# bot_schem_rev3.net
KiCad netlist of a schematic drawn in Altium Designer
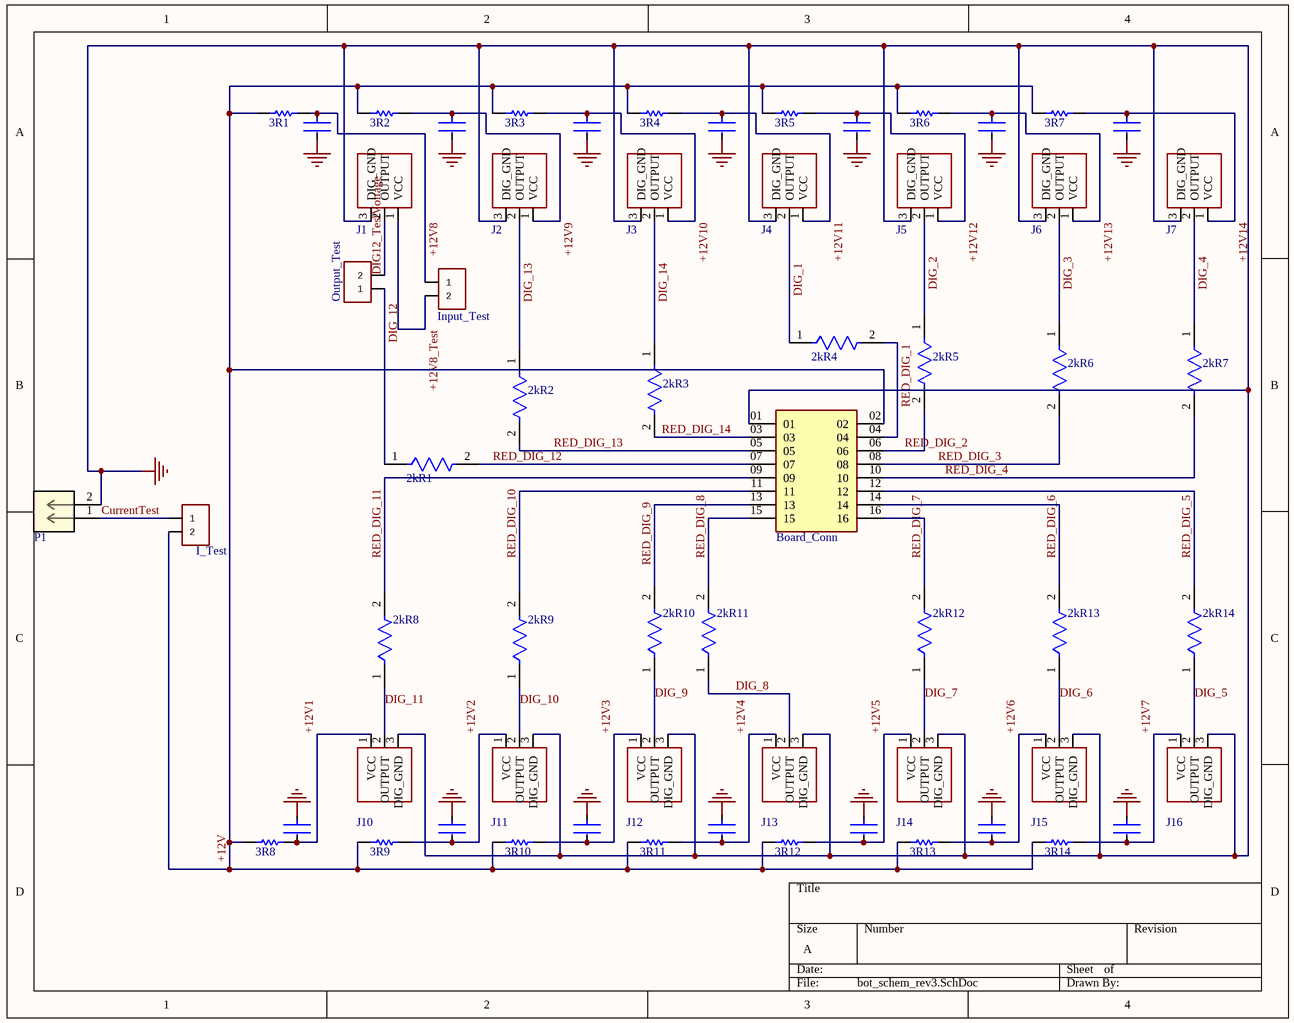
[diagram p0: bot_schem_rev3.SchDoc]

(export (version "E")
  (design (tool "Eeschema 10.0.6"))
  (components
    (comp (ref "2kR1")
      (value "CRCW06031K80FKEA")
      (footprint "2kOhm")
      (description "Res Thick Film 0603 1.8K Ohm 1% 1/10W ±100ppm/°C Molded SMD Paper T/R")
      (fields (field (name "MANUFACTURER") "Vishay") (field (name "TOLERANCE") "1%"))
      (libsource (lib "ps_schlib") (part "CRCW06031K80FKEA"))
    )
    (comp (ref "2kR2")
      (value "CRCW06031K80FKEA")
      (footprint "2kOhm")
      (description "Res Thick Film 0603 1.8K Ohm 1% 1/10W ±100ppm/°C Molded SMD Paper T/R")
      (fields (field (name "MANUFACTURER") "Vishay") (field (name "TOLERANCE") "1%"))
      (libsource (lib "ps_schlib") (part "CRCW06031K80FKEA"))
    )
    (comp (ref "2kR3")
      (value "CRCW06031K80FKEA")
      (footprint "2kOhm")
      (description "Res Thick Film 0603 1.8K Ohm 1% 1/10W ±100ppm/°C Molded SMD Paper T/R")
      (fields (field (name "MANUFACTURER") "Vishay") (field (name "TOLERANCE") "1%"))
      (libsource (lib "ps_schlib") (part "CRCW06031K80FKEA"))
    )
    (comp (ref "2kR4")
      (value "CRCW06031K80FKEA")
      (footprint "2kOhm")
      (description "Res Thick Film 0603 1.8K Ohm 1% 1/10W ±100ppm/°C Molded SMD Paper T/R")
      (fields (field (name "MANUFACTURER") "Vishay") (field (name "TOLERANCE") "1%"))
      (libsource (lib "ps_schlib") (part "CRCW06031K80FKEA"))
    )
    (comp (ref "2kR5")
      (value "CRCW06031K80FKEA")
      (footprint "2kOhm")
      (description "Res Thick Film 0603 1.8K Ohm 1% 1/10W ±100ppm/°C Molded SMD Paper T/R")
      (fields (field (name "MANUFACTURER") "Vishay") (field (name "TOLERANCE") "1%"))
      (libsource (lib "ps_schlib") (part "CRCW06031K80FKEA"))
    )
    (comp (ref "2kR6")
      (value "CRCW06031K80FKEA")
      (footprint "2kOhm")
      (description "Res Thick Film 0603 1.8K Ohm 1% 1/10W ±100ppm/°C Molded SMD Paper T/R")
      (fields (field (name "MANUFACTURER") "Vishay") (field (name "TOLERANCE") "1%"))
      (libsource (lib "ps_schlib") (part "CRCW06031K80FKEA"))
    )
    (comp (ref "2kR7")
      (value "CRCW06031K80FKEA")
      (footprint "2kOhm")
      (description "Res Thick Film 0603 1.8K Ohm 1% 1/10W ±100ppm/°C Molded SMD Paper T/R")
      (fields (field (name "MANUFACTURER") "Vishay") (field (name "TOLERANCE") "1%"))
      (libsource (lib "ps_schlib") (part "CRCW06031K80FKEA"))
    )
    (comp (ref "2kR8")
      (value "CRCW06031K80FKEA")
      (footprint "2kOhm")
      (description "Res Thick Film 0603 1.8K Ohm 1% 1/10W ±100ppm/°C Molded SMD Paper T/R")
      (fields (field (name "MANUFACTURER") "Vishay") (field (name "TOLERANCE") "1%"))
      (libsource (lib "ps_schlib") (part "CRCW06031K80FKEA"))
    )
    (comp (ref "2kR9")
      (value "CRCW06031K80FKEA")
      (footprint "2kOhm")
      (description "Res Thick Film 0603 1.8K Ohm 1% 1/10W ±100ppm/°C Molded SMD Paper T/R")
      (fields (field (name "MANUFACTURER") "Vishay") (field (name "TOLERANCE") "1%"))
      (libsource (lib "ps_schlib") (part "CRCW06031K80FKEA"))
    )
    (comp (ref "2kR10")
      (value "CRCW06031K80FKEA")
      (footprint "2kOhm")
      (description "Res Thick Film 0603 1.8K Ohm 1% 1/10W ±100ppm/°C Molded SMD Paper T/R")
      (fields (field (name "MANUFACTURER") "Vishay") (field (name "TOLERANCE") "1%"))
      (libsource (lib "ps_schlib") (part "CRCW06031K80FKEA"))
    )
    (comp (ref "2kR11")
      (value "CRCW06031K80FKEA")
      (footprint "2kOhm")
      (description "Res Thick Film 0603 1.8K Ohm 1% 1/10W ±100ppm/°C Molded SMD Paper T/R")
      (fields (field (name "MANUFACTURER") "Vishay") (field (name "TOLERANCE") "1%"))
      (libsource (lib "ps_schlib") (part "CRCW06031K80FKEA"))
    )
    (comp (ref "2kR12")
      (value "CRCW06031K80FKEA")
      (footprint "2kOhm")
      (description "Res Thick Film 0603 1.8K Ohm 1% 1/10W ±100ppm/°C Molded SMD Paper T/R")
      (fields (field (name "MANUFACTURER") "Vishay") (field (name "TOLERANCE") "1%"))
      (libsource (lib "ps_schlib") (part "CRCW06031K80FKEA"))
    )
    (comp (ref "2kR13")
      (value "CRCW06031K80FKEA")
      (footprint "2kOhm")
      (description "Res Thick Film 0603 1.8K Ohm 1% 1/10W ±100ppm/°C Molded SMD Paper T/R")
      (fields (field (name "MANUFACTURER") "Vishay") (field (name "TOLERANCE") "1%"))
      (libsource (lib "ps_schlib") (part "CRCW06031K80FKEA"))
    )
    (comp (ref "2kR14")
      (value "CRCW06031K80FKEA")
      (footprint "2kOhm")
      (description "Res Thick Film 0603 1.8K Ohm 1% 1/10W ±100ppm/°C Molded SMD Paper T/R")
      (fields (field (name "MANUFACTURER") "Vishay") (field (name "TOLERANCE") "1%"))
      (libsource (lib "ps_schlib") (part "CRCW06031K80FKEA"))
    )
    (comp (ref "3R1")
      (value "ERJ-2BQJR30X")
      (footprint "03 Ohm")
      (description "RES 0.3 OHM 5% 1/6W 0402")
      (fields (field (name "MANUFACTURER") "Panasonic") (field (name "TOLERANCE") "5%"))
      (libsource (lib "ps_schlib") (part "ERJ-2BQJR30X"))
    )
    (comp (ref "3R2")
      (value "ERJ-2BQJR30X")
      (footprint "03 Ohm")
      (description "RES 0.3 OHM 5% 1/6W 0402")
      (fields (field (name "MANUFACTURER") "Panasonic") (field (name "TOLERANCE") "5%"))
      (libsource (lib "ps_schlib") (part "ERJ-2BQJR30X"))
    )
    (comp (ref "3R3")
      (value "ERJ-2BQJR30X")
      (footprint "03 Ohm")
      (description "RES 0.3 OHM 5% 1/6W 0402")
      (fields (field (name "MANUFACTURER") "Panasonic") (field (name "TOLERANCE") "5%"))
      (libsource (lib "ps_schlib") (part "ERJ-2BQJR30X"))
    )
    (comp (ref "3R4")
      (value "ERJ-2BQJR30X")
      (footprint "03 Ohm")
      (description "RES 0.3 OHM 5% 1/6W 0402")
      (fields (field (name "MANUFACTURER") "Panasonic") (field (name "TOLERANCE") "5%"))
      (libsource (lib "ps_schlib") (part "ERJ-2BQJR30X"))
    )
    (comp (ref "3R5")
      (value "ERJ-2BQJR30X")
      (footprint "03 Ohm")
      (description "RES 0.3 OHM 5% 1/6W 0402")
      (fields (field (name "MANUFACTURER") "Panasonic") (field (name "TOLERANCE") "5%"))
      (libsource (lib "ps_schlib") (part "ERJ-2BQJR30X"))
    )
    (comp (ref "3R6")
      (value "ERJ-2BQJR30X")
      (footprint "03 Ohm")
      (description "RES 0.3 OHM 5% 1/6W 0402")
      (fields (field (name "MANUFACTURER") "Panasonic") (field (name "TOLERANCE") "5%"))
      (libsource (lib "ps_schlib") (part "ERJ-2BQJR30X"))
    )
    (comp (ref "3R7")
      (value "ERJ-2BQJR30X")
      (footprint "03 Ohm")
      (description "RES 0.3 OHM 5% 1/6W 0402")
      (fields (field (name "MANUFACTURER") "Panasonic") (field (name "TOLERANCE") "5%"))
      (libsource (lib "ps_schlib") (part "ERJ-2BQJR30X"))
    )
    (comp (ref "3R8")
      (value "ERJ-2BQJR30X")
      (footprint "03 Ohm")
      (description "RES 0.3 OHM 5% 1/6W 0402")
      (fields (field (name "MANUFACTURER") "Panasonic") (field (name "TOLERANCE") "5%"))
      (libsource (lib "ps_schlib") (part "ERJ-2BQJR30X"))
    )
    (comp (ref "3R9")
      (value "ERJ-2BQJR30X")
      (footprint "03 Ohm")
      (description "RES 0.3 OHM 5% 1/6W 0402")
      (fields (field (name "MANUFACTURER") "Panasonic") (field (name "TOLERANCE") "5%"))
      (libsource (lib "ps_schlib") (part "ERJ-2BQJR30X"))
    )
    (comp (ref "3R10")
      (value "ERJ-2BQJR30X")
      (footprint "03 Ohm")
      (description "RES 0.3 OHM 5% 1/6W 0402")
      (fields (field (name "MANUFACTURER") "Panasonic") (field (name "TOLERANCE") "5%"))
      (libsource (lib "ps_schlib") (part "ERJ-2BQJR30X"))
    )
    (comp (ref "3R11")
      (value "ERJ-2BQJR30X")
      (footprint "03 Ohm")
      (description "RES 0.3 OHM 5% 1/6W 0402")
      (fields (field (name "MANUFACTURER") "Panasonic") (field (name "TOLERANCE") "5%"))
      (libsource (lib "ps_schlib") (part "ERJ-2BQJR30X"))
    )
    (comp (ref "3R12")
      (value "ERJ-2BQJR30X")
      (footprint "03 Ohm")
      (description "RES 0.3 OHM 5% 1/6W 0402")
      (fields (field (name "MANUFACTURER") "Panasonic") (field (name "TOLERANCE") "5%"))
      (libsource (lib "ps_schlib") (part "ERJ-2BQJR30X"))
    )
    (comp (ref "3R13")
      (value "ERJ-2BQJR30X")
      (footprint "03 Ohm")
      (description "RES 0.3 OHM 5% 1/6W 0402")
      (fields (field (name "MANUFACTURER") "Panasonic") (field (name "TOLERANCE") "5%"))
      (libsource (lib "ps_schlib") (part "ERJ-2BQJR30X"))
    )
    (comp (ref "3R14")
      (value "ERJ-2BQJR30X")
      (footprint "03 Ohm")
      (description "RES 0.3 OHM 5% 1/6W 0402")
      (fields (field (name "MANUFACTURER") "Panasonic") (field (name "TOLERANCE") "5%"))
      (libsource (lib "ps_schlib") (part "ERJ-2BQJR30X"))
    )
    (comp (ref "Board_Conn")
      (value "HW-08-11-F-D-511-SM")
      (footprint "16 pin receiver")
      (libsource (lib "ps_schlib") (part "HW-08-11-F-D-507-SM"))
    )
    (comp (ref "C1")
      (value "C0805C104K5RACTU")
      (footprint "100nF")
      (description "Cap Ceramic 0.1uF 50V X7R 10% SMD 2.0 x 1.2 mm 125 C Paper T/R")
      (fields (field (name "MANUFACTURER") "KEMET") (field (name "TOLERANCE") "10%"))
      (libsource (lib "ps_schlib") (part "C0805C104K5RACTU"))
    )
    (comp (ref "C2")
      (value "C0805C104K5RACTU")
      (footprint "100nF")
      (description "Cap Ceramic 0.1uF 50V X7R 10% SMD 2.0 x 1.2 mm 125 C Paper T/R")
      (fields (field (name "MANUFACTURER") "KEMET") (field (name "TOLERANCE") "10%"))
      (libsource (lib "ps_schlib") (part "C0805C104K5RACTU"))
    )
    (comp (ref "C3")
      (value "C0805C104K5RACTU")
      (footprint "100nF")
      (description "Cap Ceramic 0.1uF 50V X7R 10% SMD 2.0 x 1.2 mm 125 C Paper T/R")
      (fields (field (name "MANUFACTURER") "KEMET") (field (name "TOLERANCE") "10%"))
      (libsource (lib "ps_schlib") (part "C0805C104K5RACTU"))
    )
    (comp (ref "C4")
      (value "C0805C104K5RACTU")
      (footprint "100nF")
      (description "Cap Ceramic 0.1uF 50V X7R 10% SMD 2.0 x 1.2 mm 125 C Paper T/R")
      (fields (field (name "MANUFACTURER") "KEMET") (field (name "TOLERANCE") "10%"))
      (libsource (lib "ps_schlib") (part "C0805C104K5RACTU"))
    )
    (comp (ref "C5")
      (value "C0805C104K5RACTU")
      (footprint "100nF")
      (description "Cap Ceramic 0.1uF 50V X7R 10% SMD 2.0 x 1.2 mm 125 C Paper T/R")
      (fields (field (name "MANUFACTURER") "KEMET") (field (name "TOLERANCE") "10%"))
      (libsource (lib "ps_schlib") (part "C0805C104K5RACTU"))
    )
    (comp (ref "C6")
      (value "C0805C104K5RACTU")
      (footprint "100nF")
      (description "Cap Ceramic 0.1uF 50V X7R 10% SMD 2.0 x 1.2 mm 125 C Paper T/R")
      (fields (field (name "MANUFACTURER") "KEMET") (field (name "TOLERANCE") "10%"))
      (libsource (lib "ps_schlib") (part "C0805C104K5RACTU"))
    )
    (comp (ref "C7")
      (value "C0805C104K5RACTU")
      (footprint "100nF")
      (description "Cap Ceramic 0.1uF 50V X7R 10% SMD 2.0 x 1.2 mm 125 C Paper T/R")
      (fields (field (name "MANUFACTURER") "KEMET") (field (name "TOLERANCE") "10%"))
      (libsource (lib "ps_schlib") (part "C0805C104K5RACTU"))
    )
    (comp (ref "C8")
      (value "C0805C104K5RACTU")
      (footprint "100nF")
      (description "Cap Ceramic 0.1uF 50V X7R 10% SMD 2.0 x 1.2 mm 125 C Paper T/R")
      (fields (field (name "MANUFACTURER") "KEMET") (field (name "TOLERANCE") "10%"))
      (libsource (lib "ps_schlib") (part "C0805C104K5RACTU"))
    )
    (comp (ref "C9")
      (value "C0805C104K5RACTU")
      (footprint "100nF")
      (description "Cap Ceramic 0.1uF 50V X7R 10% SMD 2.0 x 1.2 mm 125 C Paper T/R")
      (fields (field (name "MANUFACTURER") "KEMET") (field (name "TOLERANCE") "10%"))
      (libsource (lib "ps_schlib") (part "C0805C104K5RACTU"))
    )
    (comp (ref "C10")
      (value "C0805C104K5RACTU")
      (footprint "100nF")
      (description "Cap Ceramic 0.1uF 50V X7R 10% SMD 2.0 x 1.2 mm 125 C Paper T/R")
      (fields (field (name "MANUFACTURER") "KEMET") (field (name "TOLERANCE") "10%"))
      (libsource (lib "ps_schlib") (part "C0805C104K5RACTU"))
    )
    (comp (ref "C11")
      (value "C0805C104K5RACTU")
      (footprint "100nF")
      (description "Cap Ceramic 0.1uF 50V X7R 10% SMD 2.0 x 1.2 mm 125 C Paper T/R")
      (fields (field (name "MANUFACTURER") "KEMET") (field (name "TOLERANCE") "10%"))
      (libsource (lib "ps_schlib") (part "C0805C104K5RACTU"))
    )
    (comp (ref "C12")
      (value "C0805C104K5RACTU")
      (footprint "100nF")
      (description "Cap Ceramic 0.1uF 50V X7R 10% SMD 2.0 x 1.2 mm 125 C Paper T/R")
      (fields (field (name "MANUFACTURER") "KEMET") (field (name "TOLERANCE") "10%"))
      (libsource (lib "ps_schlib") (part "C0805C104K5RACTU"))
    )
    (comp (ref "C13")
      (value "C0805C104K5RACTU")
      (footprint "100nF")
      (description "Cap Ceramic 0.1uF 50V X7R 10% SMD 2.0 x 1.2 mm 125 C Paper T/R")
      (fields (field (name "MANUFACTURER") "KEMET") (field (name "TOLERANCE") "10%"))
      (libsource (lib "ps_schlib") (part "C0805C104K5RACTU"))
    )
    (comp (ref "C14")
      (value "C0805C104K5RACTU")
      (footprint "100nF")
      (description "Cap Ceramic 0.1uF 50V X7R 10% SMD 2.0 x 1.2 mm 125 C Paper T/R")
      (fields (field (name "MANUFACTURER") "KEMET") (field (name "TOLERANCE") "10%"))
      (libsource (lib "ps_schlib") (part "C0805C104K5RACTU"))
    )
    (comp (ref "Input_Test")
      (value "PRPC001DFAN-RC")
      (footprint "PRPC001DFAN-RC")
      (description "Conn Header Vert 2POS")
      (fields (field (name "MANUFACTURER") "Sullins"))
      (libsource (lib "ps_schlib") (part "PRPC001DFAN-RC"))
    )
    (comp (ref "I_Test")
      (value "PRPC001DFAN-RC")
      (footprint "PRPC001DFAN-RC")
      (description "Conn Header Vert 2POS")
      (fields (field (name "MANUFACTURER") "Sullins"))
      (libsource (lib "ps_schlib") (part "PRPC001DFAN-RC"))
    )
    (comp (ref "J1")
      (value "IF-D95T")
      (footprint "IF-D95")
      (description "DETECTOR PHOTOLOGIC TTL/CMOS")
      (fields (field (name "MANUFACTURER") "Industrial Fiber Optics"))
      (libsource (lib "ps_schlib") (part "IF-D95T"))
    )
    (comp (ref "J2")
      (value "IF-D95T")
      (footprint "IF-D95")
      (description "DETECTOR PHOTOLOGIC TTL/CMOS")
      (fields (field (name "MANUFACTURER") "Industrial Fiber Optics"))
      (libsource (lib "ps_schlib") (part "IF-D95T"))
    )
    (comp (ref "J3")
      (value "IF-D95T")
      (footprint "IF-D95")
      (description "DETECTOR PHOTOLOGIC TTL/CMOS")
      (fields (field (name "MANUFACTURER") "Industrial Fiber Optics"))
      (libsource (lib "ps_schlib") (part "IF-D95T"))
    )
    (comp (ref "J4")
      (value "IF-D95T")
      (footprint "IF-D95")
      (description "DETECTOR PHOTOLOGIC TTL/CMOS")
      (fields (field (name "MANUFACTURER") "Industrial Fiber Optics"))
      (libsource (lib "ps_schlib") (part "IF-D95T"))
    )
    (comp (ref "J5")
      (value "IF-D95T")
      (footprint "IF-D95")
      (description "DETECTOR PHOTOLOGIC TTL/CMOS")
      (fields (field (name "MANUFACTURER") "Industrial Fiber Optics"))
      (libsource (lib "ps_schlib") (part "IF-D95T"))
    )
    (comp (ref "J6")
      (value "IF-D95T")
      (footprint "IF-D95")
      (description "DETECTOR PHOTOLOGIC TTL/CMOS")
      (fields (field (name "MANUFACTURER") "Industrial Fiber Optics"))
      (libsource (lib "ps_schlib") (part "IF-D95T"))
    )
    (comp (ref "J7")
      (value "IF-D95T")
      (footprint "IF-D95")
      (description "DETECTOR PHOTOLOGIC TTL/CMOS")
      (fields (field (name "MANUFACTURER") "Industrial Fiber Optics"))
      (libsource (lib "ps_schlib") (part "IF-D95T"))
    )
    (comp (ref "J10")
      (value "IF-D95T")
      (footprint "IF-D95")
      (description "DETECTOR PHOTOLOGIC TTL/CMOS")
      (fields (field (name "MANUFACTURER") "Industrial Fiber Optics"))
      (libsource (lib "ps_schlib") (part "IF-D95T"))
    )
    (comp (ref "J11")
      (value "IF-D95T")
      (footprint "IF-D95")
      (description "DETECTOR PHOTOLOGIC TTL/CMOS")
      (fields (field (name "MANUFACTURER") "Industrial Fiber Optics"))
      (libsource (lib "ps_schlib") (part "IF-D95T"))
    )
    (comp (ref "J12")
      (value "IF-D95T")
      (footprint "IF-D95")
      (description "DETECTOR PHOTOLOGIC TTL/CMOS")
      (fields (field (name "MANUFACTURER") "Industrial Fiber Optics"))
      (libsource (lib "ps_schlib") (part "IF-D95T"))
    )
    (comp (ref "J13")
      (value "IF-D95T")
      (footprint "IF-D95")
      (description "DETECTOR PHOTOLOGIC TTL/CMOS")
      (fields (field (name "MANUFACTURER") "Industrial Fiber Optics"))
      (libsource (lib "ps_schlib") (part "IF-D95T"))
    )
    (comp (ref "J14")
      (value "IF-D95T")
      (footprint "IF-D95")
      (description "DETECTOR PHOTOLOGIC TTL/CMOS")
      (fields (field (name "MANUFACTURER") "Industrial Fiber Optics"))
      (libsource (lib "ps_schlib") (part "IF-D95T"))
    )
    (comp (ref "J15")
      (value "IF-D95T")
      (footprint "IF-D95")
      (description "DETECTOR PHOTOLOGIC TTL/CMOS")
      (fields (field (name "MANUFACTURER") "Industrial Fiber Optics"))
      (libsource (lib "ps_schlib") (part "IF-D95T"))
    )
    (comp (ref "J16")
      (value "IF-D95T")
      (footprint "IF-D95")
      (description "DETECTOR PHOTOLOGIC TTL/CMOS")
      (fields (field (name "MANUFACTURER") "Industrial Fiber Optics"))
      (libsource (lib "ps_schlib") (part "IF-D95T"))
    )
    (comp (ref "Output_Test")
      (value "PRPC001DFAN-RC")
      (footprint "PRPC001DFAN-RC")
      (description "Conn Header Vert 2POS")
      (fields (field (name "MANUFACTURER") "Sullins"))
      (libsource (lib "ps_schlib") (part "PRPC001DFAN-RC"))
    )
    (comp (ref "P1")
      (value "1054311102")
      (footprint "CONN_1054311102_MOL")
      (fields (field (name "MANUFACTURER") "Molex"))
      (libsource (lib "ps_schlib") (part "1054311102"))
    )
  )
  (nets
    (net (code "1") (name "/+12V") (class "Default")
      (node (ref "3R1") (pin "1") (pinfunction "1_1") (pintype "passive"))
      (node (ref "3R10") (pin "1") (pinfunction "1_1") (pintype "passive"))
      (node (ref "3R11") (pin "1") (pinfunction "1_1") (pintype "passive"))
      (node (ref "3R12") (pin "1") (pinfunction "1_1") (pintype "passive"))
      (node (ref "3R13") (pin "1") (pinfunction "1_1") (pintype "passive"))
      (node (ref "3R14") (pin "1") (pinfunction "1_1") (pintype "passive"))
      (node (ref "3R2") (pin "1") (pinfunction "1_1") (pintype "passive"))
      (node (ref "3R3") (pin "1") (pinfunction "1_1") (pintype "passive"))
      (node (ref "3R4") (pin "1") (pinfunction "1_1") (pintype "passive"))
      (node (ref "3R5") (pin "1") (pinfunction "1_1") (pintype "passive"))
      (node (ref "3R6") (pin "1") (pinfunction "1_1") (pintype "passive"))
      (node (ref "3R7") (pin "1") (pinfunction "1_1") (pintype "passive"))
      (node (ref "3R8") (pin "1") (pinfunction "1_1") (pintype "passive"))
      (node (ref "3R9") (pin "1") (pinfunction "1_1") (pintype "passive"))
      (node (ref "Board_Conn") (pin "02") (pinfunction "02_02") (pintype "passive"))
      (node (ref "I_Test") (pin "2") (pinfunction "2_2") (pintype "passive"))
    )
    (net (code "2") (name "/+12V1") (class "Default")
      (node (ref "3R8") (pin "2") (pinfunction "2_2") (pintype "passive"))
      (node (ref "C8") (pin "2") (pinfunction "2_2") (pintype "passive"))
      (node (ref "J10") (pin "1") (pinfunction "VCC_1") (pintype "passive"))
    )
    (net (code "3") (name "/+12V2") (class "Default")
      (node (ref "3R9") (pin "2") (pinfunction "2_2") (pintype "passive"))
      (node (ref "C9") (pin "2") (pinfunction "2_2") (pintype "passive"))
      (node (ref "J11") (pin "1") (pinfunction "VCC_1") (pintype "passive"))
    )
    (net (code "4") (name "/+12V3") (class "Default")
      (node (ref "3R10") (pin "2") (pinfunction "2_2") (pintype "passive"))
      (node (ref "C10") (pin "2") (pinfunction "2_2") (pintype "passive"))
      (node (ref "J12") (pin "1") (pinfunction "VCC_1") (pintype "passive"))
    )
    (net (code "5") (name "/+12V4") (class "Default")
      (node (ref "3R11") (pin "2") (pinfunction "2_2") (pintype "passive"))
      (node (ref "C11") (pin "2") (pinfunction "2_2") (pintype "passive"))
      (node (ref "J13") (pin "1") (pinfunction "VCC_1") (pintype "passive"))
    )
    (net (code "6") (name "/+12V5") (class "Default")
      (node (ref "3R12") (pin "2") (pinfunction "2_2") (pintype "passive"))
      (node (ref "C12") (pin "2") (pinfunction "2_2") (pintype "passive"))
      (node (ref "J14") (pin "1") (pinfunction "VCC_1") (pintype "passive"))
    )
    (net (code "7") (name "/+12V6") (class "Default")
      (node (ref "3R13") (pin "2") (pinfunction "2_2") (pintype "passive"))
      (node (ref "C13") (pin "2") (pinfunction "2_2") (pintype "passive"))
      (node (ref "J15") (pin "1") (pinfunction "VCC_1") (pintype "passive"))
    )
    (net (code "8") (name "/+12V7") (class "Default")
      (node (ref "3R14") (pin "2") (pinfunction "2_2") (pintype "passive"))
      (node (ref "C14") (pin "2") (pinfunction "2_2") (pintype "passive"))
      (node (ref "J16") (pin "1") (pinfunction "VCC_1") (pintype "passive"))
    )
    (net (code "9") (name "/+12V8") (class "Default")
      (node (ref "3R1") (pin "2") (pinfunction "2_2") (pintype "passive"))
      (node (ref "C1") (pin "1") (pinfunction "1_1") (pintype "passive"))
      (node (ref "Input_Test") (pin "1") (pinfunction "1_1") (pintype "passive"))
    )
    (net (code "10") (name "/+12V8_Test") (class "Default")
      (node (ref "Input_Test") (pin "2") (pinfunction "2_2") (pintype "passive"))
      (node (ref "J1") (pin "1") (pinfunction "VCC_1") (pintype "passive"))
    )
    (net (code "11") (name "/+12V9") (class "Default")
      (node (ref "3R2") (pin "2") (pinfunction "2_2") (pintype "passive"))
      (node (ref "C2") (pin "1") (pinfunction "1_1") (pintype "passive"))
      (node (ref "J2") (pin "1") (pinfunction "VCC_1") (pintype "passive"))
    )
    (net (code "12") (name "/+12V10") (class "Default")
      (node (ref "3R3") (pin "2") (pinfunction "2_2") (pintype "passive"))
      (node (ref "C3") (pin "1") (pinfunction "1_1") (pintype "passive"))
      (node (ref "J3") (pin "1") (pinfunction "VCC_1") (pintype "passive"))
    )
    (net (code "13") (name "/+12V11") (class "Default")
      (node (ref "3R4") (pin "2") (pinfunction "2_2") (pintype "passive"))
      (node (ref "C4") (pin "1") (pinfunction "1_1") (pintype "passive"))
      (node (ref "J4") (pin "1") (pinfunction "VCC_1") (pintype "passive"))
    )
    (net (code "14") (name "/+12V12") (class "Default")
      (node (ref "3R5") (pin "2") (pinfunction "2_2") (pintype "passive"))
      (node (ref "C5") (pin "1") (pinfunction "1_1") (pintype "passive"))
      (node (ref "J5") (pin "1") (pinfunction "VCC_1") (pintype "passive"))
    )
    (net (code "15") (name "/+12V13") (class "Default")
      (node (ref "3R6") (pin "2") (pinfunction "2_2") (pintype "passive"))
      (node (ref "C6") (pin "1") (pinfunction "1_1") (pintype "passive"))
      (node (ref "J6") (pin "1") (pinfunction "VCC_1") (pintype "passive"))
    )
    (net (code "16") (name "/+12V14") (class "Default")
      (node (ref "3R7") (pin "2") (pinfunction "2_2") (pintype "passive"))
      (node (ref "C7") (pin "1") (pinfunction "1_1") (pintype "passive"))
      (node (ref "J7") (pin "1") (pinfunction "VCC_1") (pintype "passive"))
    )
    (net (code "18") (name "/CurrentTest") (class "Default")
      (node (ref "I_Test") (pin "1") (pinfunction "1_1") (pintype "passive"))
      (node (ref "P1") (pin "1") (pinfunction "1_1") (pintype "passive"))
    )
    (net (code "19") (name "/DIG12_TestVoltage") (class "Default")
      (node (ref "J1") (pin "2") (pinfunction "OUTPUT_2") (pintype "passive"))
      (node (ref "Output_Test") (pin "2") (pinfunction "2_2") (pintype "passive"))
    )
    (net (code "20") (name "/DIG_1") (class "Default")
      (node (ref "2kR4") (pin "1") (pinfunction "1_1") (pintype "passive"))
      (node (ref "J4") (pin "2") (pinfunction "OUTPUT_2") (pintype "passive"))
    )
    (net (code "21") (name "/DIG_2") (class "Default")
      (node (ref "2kR5") (pin "1") (pinfunction "1_1") (pintype "passive"))
      (node (ref "J5") (pin "2") (pinfunction "OUTPUT_2") (pintype "passive"))
    )
    (net (code "22") (name "/DIG_3") (class "Default")
      (node (ref "2kR6") (pin "1") (pinfunction "1_1") (pintype "passive"))
      (node (ref "J6") (pin "2") (pinfunction "OUTPUT_2") (pintype "passive"))
    )
    (net (code "23") (name "/DIG_4") (class "Default")
      (node (ref "2kR7") (pin "1") (pinfunction "1_1") (pintype "passive"))
      (node (ref "J7") (pin "2") (pinfunction "OUTPUT_2") (pintype "passive"))
    )
    (net (code "24") (name "/DIG_5") (class "Default")
      (node (ref "2kR14") (pin "1") (pinfunction "1_1") (pintype "passive"))
      (node (ref "J16") (pin "2") (pinfunction "OUTPUT_2") (pintype "passive"))
    )
    (net (code "25") (name "/DIG_6") (class "Default")
      (node (ref "2kR13") (pin "1") (pinfunction "1_1") (pintype "passive"))
      (node (ref "J15") (pin "2") (pinfunction "OUTPUT_2") (pintype "passive"))
    )
    (net (code "26") (name "/DIG_7") (class "Default")
      (node (ref "2kR12") (pin "1") (pinfunction "1_1") (pintype "passive"))
      (node (ref "J14") (pin "2") (pinfunction "OUTPUT_2") (pintype "passive"))
    )
    (net (code "27") (name "/DIG_8") (class "Default")
      (node (ref "2kR11") (pin "1") (pinfunction "1_1") (pintype "passive"))
      (node (ref "J13") (pin "2") (pinfunction "OUTPUT_2") (pintype "passive"))
    )
    (net (code "28") (name "/DIG_9") (class "Default")
      (node (ref "2kR10") (pin "1") (pinfunction "1_1") (pintype "passive"))
      (node (ref "J12") (pin "2") (pinfunction "OUTPUT_2") (pintype "passive"))
    )
    (net (code "29") (name "/DIG_10") (class "Default")
      (node (ref "2kR9") (pin "1") (pinfunction "1_1") (pintype "passive"))
      (node (ref "J11") (pin "2") (pinfunction "OUTPUT_2") (pintype "passive"))
    )
    (net (code "30") (name "/DIG_11") (class "Default")
      (node (ref "2kR8") (pin "1") (pinfunction "1_1") (pintype "passive"))
      (node (ref "J10") (pin "2") (pinfunction "OUTPUT_2") (pintype "passive"))
    )
    (net (code "31") (name "/DIG_12") (class "Default")
      (node (ref "2kR1") (pin "1") (pinfunction "1_1") (pintype "passive"))
      (node (ref "Output_Test") (pin "1") (pinfunction "1_1") (pintype "passive"))
    )
    (net (code "32") (name "/DIG_13") (class "Default")
      (node (ref "2kR2") (pin "1") (pinfunction "1_1") (pintype "passive"))
      (node (ref "J2") (pin "2") (pinfunction "OUTPUT_2") (pintype "passive"))
    )
    (net (code "33") (name "/DIG_14") (class "Default")
      (node (ref "2kR3") (pin "1") (pinfunction "1_1") (pintype "passive"))
      (node (ref "J3") (pin "2") (pinfunction "OUTPUT_2") (pintype "passive"))
    )
    (net (code "34") (name "/RED_DIG_1") (class "Default")
      (node (ref "2kR4") (pin "2") (pinfunction "2_2") (pintype "passive"))
      (node (ref "Board_Conn") (pin "04") (pinfunction "04_04") (pintype "passive"))
    )
    (net (code "35") (name "/RED_DIG_2") (class "Default")
      (node (ref "2kR5") (pin "2") (pinfunction "2_2") (pintype "passive"))
      (node (ref "Board_Conn") (pin "06") (pinfunction "06_06") (pintype "passive"))
    )
    (net (code "36") (name "/RED_DIG_3") (class "Default")
      (node (ref "2kR6") (pin "2") (pinfunction "2_2") (pintype "passive"))
      (node (ref "Board_Conn") (pin "08") (pinfunction "08_08") (pintype "passive"))
    )
    (net (code "37") (name "/RED_DIG_4") (class "Default")
      (node (ref "2kR7") (pin "2") (pinfunction "2_2") (pintype "passive"))
      (node (ref "Board_Conn") (pin "10") (pinfunction "10_10") (pintype "passive"))
    )
    (net (code "38") (name "/RED_DIG_5") (class "Default")
      (node (ref "2kR14") (pin "2") (pinfunction "2_2") (pintype "passive"))
      (node (ref "Board_Conn") (pin "12") (pinfunction "12_12") (pintype "passive"))
    )
    (net (code "39") (name "/RED_DIG_6") (class "Default")
      (node (ref "2kR13") (pin "2") (pinfunction "2_2") (pintype "passive"))
      (node (ref "Board_Conn") (pin "14") (pinfunction "14_14") (pintype "passive"))
    )
    (net (code "40") (name "/RED_DIG_7") (class "Default")
      (node (ref "2kR12") (pin "2") (pinfunction "2_2") (pintype "passive"))
      (node (ref "Board_Conn") (pin "16") (pinfunction "16_16") (pintype "passive"))
    )
    (net (code "41") (name "/RED_DIG_8") (class "Default")
      (node (ref "2kR11") (pin "2") (pinfunction "2_2") (pintype "passive"))
      (node (ref "Board_Conn") (pin "15") (pinfunction "15_15") (pintype "passive"))
    )
    (net (code "42") (name "/RED_DIG_9") (class "Default")
      (node (ref "2kR10") (pin "2") (pinfunction "2_2") (pintype "passive"))
      (node (ref "Board_Conn") (pin "13") (pinfunction "13_13") (pintype "passive"))
    )
    (net (code "43") (name "/RED_DIG_10") (class "Default")
      (node (ref "2kR9") (pin "2") (pinfunction "2_2") (pintype "passive"))
      (node (ref "Board_Conn") (pin "11") (pinfunction "11_11") (pintype "passive"))
    )
    (net (code "44") (name "/RED_DIG_11") (class "Default")
      (node (ref "2kR8") (pin "2") (pinfunction "2_2") (pintype "passive"))
      (node (ref "Board_Conn") (pin "09") (pinfunction "09_09") (pintype "passive"))
    )
    (net (code "45") (name "/RED_DIG_12") (class "Default")
      (node (ref "2kR1") (pin "2") (pinfunction "2_2") (pintype "passive"))
      (node (ref "Board_Conn") (pin "07") (pinfunction "07_07") (pintype "passive"))
    )
    (net (code "46") (name "/RED_DIG_13") (class "Default")
      (node (ref "2kR2") (pin "2") (pinfunction "2_2") (pintype "passive"))
      (node (ref "Board_Conn") (pin "05") (pinfunction "05_05") (pintype "passive"))
    )
    (net (code "47") (name "/RED_DIG_14") (class "Default")
      (node (ref "2kR3") (pin "2") (pinfunction "2_2") (pintype "passive"))
      (node (ref "Board_Conn") (pin "03") (pinfunction "03_03") (pintype "passive"))
    )
    (net (code "48") (name "GND") (class "Default")
      (node (ref "Board_Conn") (pin "01") (pinfunction "01_01") (pintype "passive"))
      (node (ref "C1") (pin "2") (pinfunction "2_2") (pintype "passive"))
      (node (ref "C10") (pin "1") (pinfunction "1_1") (pintype "passive"))
      (node (ref "C11") (pin "1") (pinfunction "1_1") (pintype "passive"))
      (node (ref "C12") (pin "1") (pinfunction "1_1") (pintype "passive"))
      (node (ref "C13") (pin "1") (pinfunction "1_1") (pintype "passive"))
      (node (ref "C14") (pin "1") (pinfunction "1_1") (pintype "passive"))
      (node (ref "C2") (pin "2") (pinfunction "2_2") (pintype "passive"))
      (node (ref "C3") (pin "2") (pinfunction "2_2") (pintype "passive"))
      (node (ref "C4") (pin "2") (pinfunction "2_2") (pintype "passive"))
      (node (ref "C5") (pin "2") (pinfunction "2_2") (pintype "passive"))
      (node (ref "C6") (pin "2") (pinfunction "2_2") (pintype "passive"))
      (node (ref "C7") (pin "2") (pinfunction "2_2") (pintype "passive"))
      (node (ref "C8") (pin "1") (pinfunction "1_1") (pintype "passive"))
      (node (ref "C9") (pin "1") (pinfunction "1_1") (pintype "passive"))
      (node (ref "J1") (pin "3") (pinfunction "DIG_GND_3") (pintype "passive"))
      (node (ref "J10") (pin "3") (pinfunction "DIG_GND_3") (pintype "passive"))
      (node (ref "J11") (pin "3") (pinfunction "DIG_GND_3") (pintype "passive"))
      (node (ref "J12") (pin "3") (pinfunction "DIG_GND_3") (pintype "passive"))
      (node (ref "J13") (pin "3") (pinfunction "DIG_GND_3") (pintype "passive"))
      (node (ref "J14") (pin "3") (pinfunction "DIG_GND_3") (pintype "passive"))
      (node (ref "J15") (pin "3") (pinfunction "DIG_GND_3") (pintype "passive"))
      (node (ref "J16") (pin "3") (pinfunction "DIG_GND_3") (pintype "passive"))
      (node (ref "J2") (pin "3") (pinfunction "DIG_GND_3") (pintype "passive"))
      (node (ref "J3") (pin "3") (pinfunction "DIG_GND_3") (pintype "passive"))
      (node (ref "J4") (pin "3") (pinfunction "DIG_GND_3") (pintype "passive"))
      (node (ref "J5") (pin "3") (pinfunction "DIG_GND_3") (pintype "passive"))
      (node (ref "J6") (pin "3") (pinfunction "DIG_GND_3") (pintype "passive"))
      (node (ref "J7") (pin "3") (pinfunction "DIG_GND_3") (pintype "passive"))
      (node (ref "P1") (pin "2") (pinfunction "2_2") (pintype "passive"))
    )
  )
)
